# S7CAS-PLEIADES-CARTE-MERE_P20_DAC.net
KiCad netlist of a schematic drawn in Altium Designer
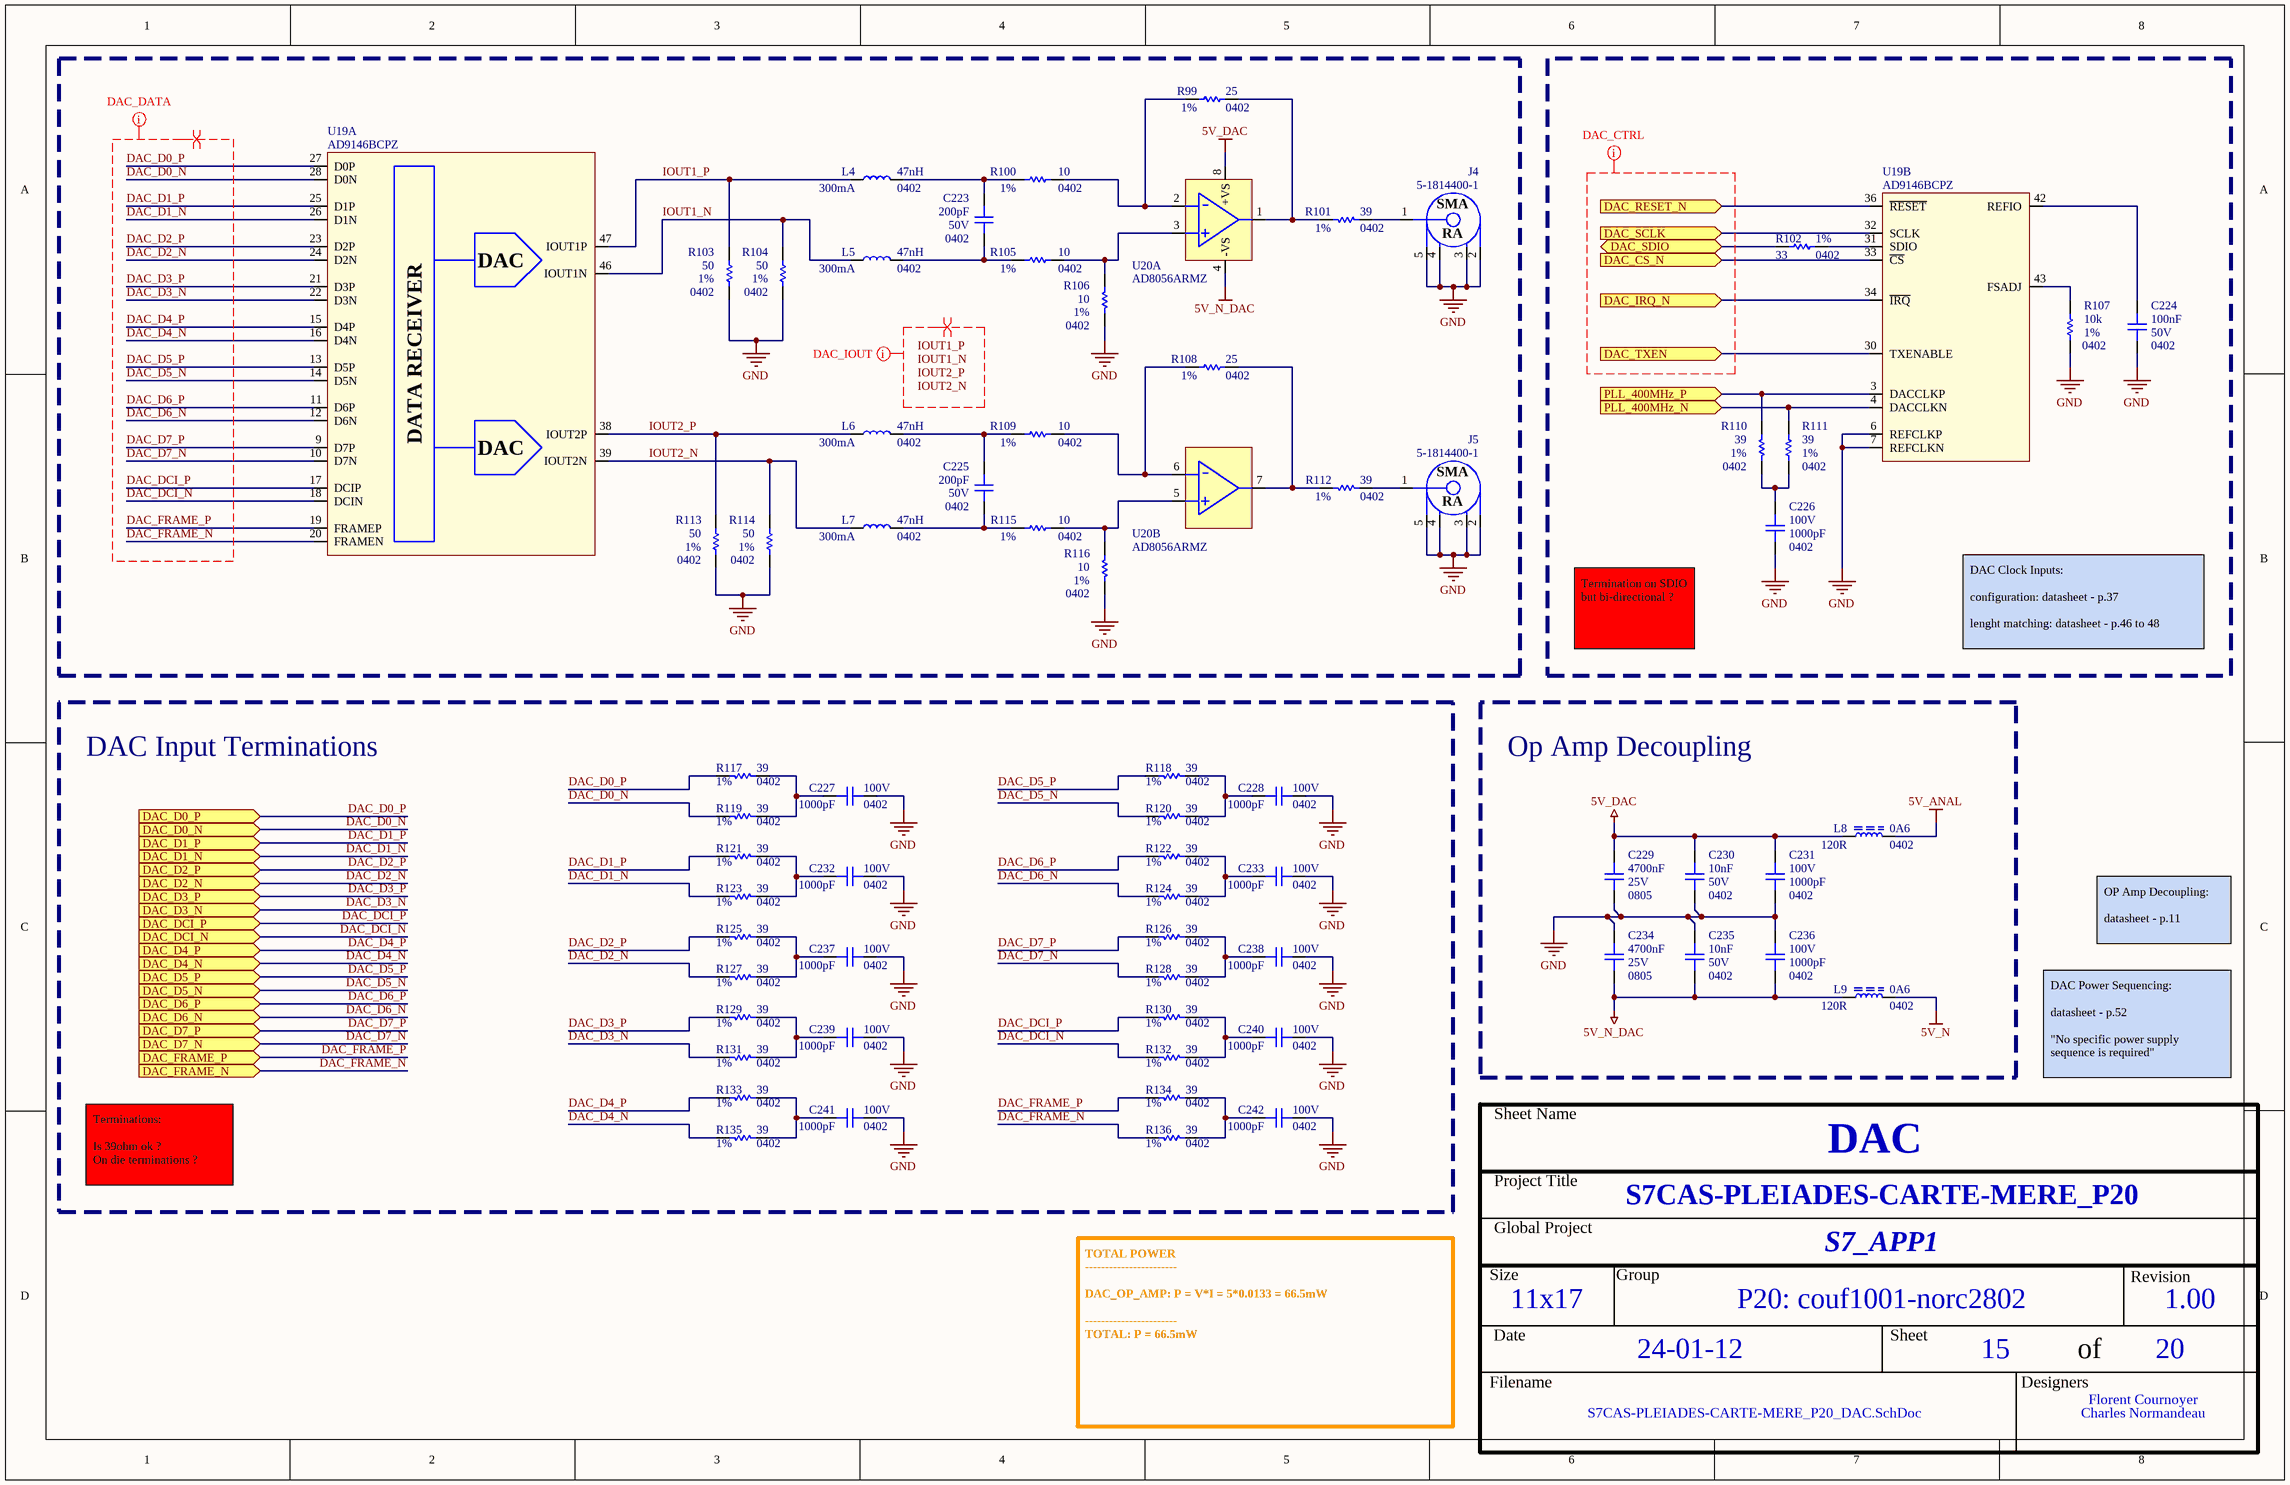
[diagram p0: S7CAS-PLEIADES-CARTE-MERE_P20_DAC.SchDoc]

(export (version "E")
  (design (tool "Eeschema 10.0.6"))
  (components
    (comp (ref "C223")
      (value "200pF")
      (footprint "CAP_0402")
      (description "CAP - 0402")
      (fields
        (field (name "MFG PART NUMBER") "GCM1555G1H201GA16")
        (field (name "VOLTAGE") "50V")
        (field (name "PACKAGE") "0402")
        (field (name "CREATEDBY") "Jonathan Bouchard")
      )
      (libsource (lib "S7CAS_LIB2023") (part "CAP - 0402"))
    )
    (comp (ref "C224")
      (value "100nF")
      (footprint "CAP_0402")
      (description "CAP - 0402")
      (fields
        (field (name "MFG PART NUMBER") "GRM155R61H104KE14")
        (field (name "VOLTAGE") "50V")
        (field (name "PACKAGE") "0402")
        (field (name "CREATEDBY") "Jonathan Bouchard")
      )
      (libsource (lib "S7CAS_LIB2023") (part "CAP - 0402"))
    )
    (comp (ref "C225")
      (value "200pF")
      (footprint "CAP_0402")
      (description "CAP - 0402")
      (fields
        (field (name "MFG PART NUMBER") "GCM1555G1H201GA16")
        (field (name "VOLTAGE") "50V")
        (field (name "PACKAGE") "0402")
        (field (name "CREATEDBY") "Jonathan Bouchard")
      )
      (libsource (lib "S7CAS_LIB2023") (part "CAP - 0402"))
    )
    (comp (ref "C226")
      (value "1000pF")
      (footprint "CAP_0402")
      (description "CAP - 0402")
      (fields
        (field (name "MFG PART NUMBER") "GRM155R72A102KA01")
        (field (name "VOLTAGE") "100V")
        (field (name "PACKAGE") "0402")
        (field (name "CREATEDBY") "Jonathan Bouchard")
      )
      (libsource (lib "S7CAS_LIB2023") (part "CAP - 0402"))
    )
    (comp (ref "C227")
      (value "1000pF")
      (footprint "CAP_0402")
      (description "CAP - 0402")
      (fields
        (field (name "MFG PART NUMBER") "GRM155R72A102KA01")
        (field (name "VOLTAGE") "100V")
        (field (name "PACKAGE") "0402")
        (field (name "CREATEDBY") "Jonathan Bouchard")
      )
      (libsource (lib "S7CAS_LIB2023") (part "CAP - 0402"))
    )
    (comp (ref "C228")
      (value "1000pF")
      (footprint "CAP_0402")
      (description "CAP - 0402")
      (fields
        (field (name "MFG PART NUMBER") "GRM155R72A102KA01")
        (field (name "VOLTAGE") "100V")
        (field (name "PACKAGE") "0402")
        (field (name "CREATEDBY") "Jonathan Bouchard")
      )
      (libsource (lib "S7CAS_LIB2023") (part "CAP - 0402"))
    )
    (comp (ref "C229")
      (value "4700nF")
      (footprint "CAP_0805")
      (description "CAP - 0805")
      (fields
        (field (name "MFG PART NUMBER") "GRM219R61E475KA73")
        (field (name "VOLTAGE") "25V")
        (field (name "PACKAGE") "0805")
        (field (name "CREATEDBY") "Jonathan Bouchard")
      )
      (libsource (lib "S7CAS_LIB2023") (part "CAP - 0805"))
    )
    (comp (ref "C230")
      (value "10nF")
      (footprint "CAP_0402")
      (description "CAP - 0402")
      (fields
        (field (name "MFG PART NUMBER") "GCM155R71H103KA55")
        (field (name "VOLTAGE") "50V")
        (field (name "PACKAGE") "0402")
        (field (name "CREATEDBY") "Jonathan Bouchard")
      )
      (libsource (lib "S7CAS_LIB2023") (part "CAP - 0402"))
    )
    (comp (ref "C231")
      (value "1000pF")
      (footprint "CAP_0402")
      (description "CAP - 0402")
      (fields
        (field (name "MFG PART NUMBER") "GRM155R72A102KA01")
        (field (name "VOLTAGE") "100V")
        (field (name "PACKAGE") "0402")
        (field (name "CREATEDBY") "Jonathan Bouchard")
      )
      (libsource (lib "S7CAS_LIB2023") (part "CAP - 0402"))
    )
    (comp (ref "C232")
      (value "1000pF")
      (footprint "CAP_0402")
      (description "CAP - 0402")
      (fields
        (field (name "MFG PART NUMBER") "GRM155R72A102KA01")
        (field (name "VOLTAGE") "100V")
        (field (name "PACKAGE") "0402")
        (field (name "CREATEDBY") "Jonathan Bouchard")
      )
      (libsource (lib "S7CAS_LIB2023") (part "CAP - 0402"))
    )
    (comp (ref "C233")
      (value "1000pF")
      (footprint "CAP_0402")
      (description "CAP - 0402")
      (fields
        (field (name "MFG PART NUMBER") "GRM155R72A102KA01")
        (field (name "VOLTAGE") "100V")
        (field (name "PACKAGE") "0402")
        (field (name "CREATEDBY") "Jonathan Bouchard")
      )
      (libsource (lib "S7CAS_LIB2023") (part "CAP - 0402"))
    )
    (comp (ref "C234")
      (value "4700nF")
      (footprint "CAP_0805")
      (description "CAP - 0805")
      (fields
        (field (name "MFG PART NUMBER") "GRM219R61E475KA73")
        (field (name "VOLTAGE") "25V")
        (field (name "PACKAGE") "0805")
        (field (name "CREATEDBY") "Jonathan Bouchard")
      )
      (libsource (lib "S7CAS_LIB2023") (part "CAP - 0805"))
    )
    (comp (ref "C235")
      (value "10nF")
      (footprint "CAP_0402")
      (description "CAP - 0402")
      (fields
        (field (name "MFG PART NUMBER") "GCM155R71H103KA55")
        (field (name "VOLTAGE") "50V")
        (field (name "PACKAGE") "0402")
        (field (name "CREATEDBY") "Jonathan Bouchard")
      )
      (libsource (lib "S7CAS_LIB2023") (part "CAP - 0402"))
    )
    (comp (ref "C236")
      (value "1000pF")
      (footprint "CAP_0402")
      (description "CAP - 0402")
      (fields
        (field (name "MFG PART NUMBER") "GRM155R72A102KA01")
        (field (name "VOLTAGE") "100V")
        (field (name "PACKAGE") "0402")
        (field (name "CREATEDBY") "Jonathan Bouchard")
      )
      (libsource (lib "S7CAS_LIB2023") (part "CAP - 0402"))
    )
    (comp (ref "C237")
      (value "1000pF")
      (footprint "CAP_0402")
      (description "CAP - 0402")
      (fields
        (field (name "MFG PART NUMBER") "GRM155R72A102KA01")
        (field (name "VOLTAGE") "100V")
        (field (name "PACKAGE") "0402")
        (field (name "CREATEDBY") "Jonathan Bouchard")
      )
      (libsource (lib "S7CAS_LIB2023") (part "CAP - 0402"))
    )
    (comp (ref "C238")
      (value "1000pF")
      (footprint "CAP_0402")
      (description "CAP - 0402")
      (fields
        (field (name "MFG PART NUMBER") "GRM155R72A102KA01")
        (field (name "VOLTAGE") "100V")
        (field (name "PACKAGE") "0402")
        (field (name "CREATEDBY") "Jonathan Bouchard")
      )
      (libsource (lib "S7CAS_LIB2023") (part "CAP - 0402"))
    )
    (comp (ref "C239")
      (value "1000pF")
      (footprint "CAP_0402")
      (description "CAP - 0402")
      (fields
        (field (name "MFG PART NUMBER") "GRM155R72A102KA01")
        (field (name "VOLTAGE") "100V")
        (field (name "PACKAGE") "0402")
        (field (name "CREATEDBY") "Jonathan Bouchard")
      )
      (libsource (lib "S7CAS_LIB2023") (part "CAP - 0402"))
    )
    (comp (ref "C240")
      (value "1000pF")
      (footprint "CAP_0402")
      (description "CAP - 0402")
      (fields
        (field (name "MFG PART NUMBER") "GRM155R72A102KA01")
        (field (name "VOLTAGE") "100V")
        (field (name "PACKAGE") "0402")
        (field (name "CREATEDBY") "Jonathan Bouchard")
      )
      (libsource (lib "S7CAS_LIB2023") (part "CAP - 0402"))
    )
    (comp (ref "C241")
      (value "1000pF")
      (footprint "CAP_0402")
      (description "CAP - 0402")
      (fields
        (field (name "MFG PART NUMBER") "GRM155R72A102KA01")
        (field (name "VOLTAGE") "100V")
        (field (name "PACKAGE") "0402")
        (field (name "CREATEDBY") "Jonathan Bouchard")
      )
      (libsource (lib "S7CAS_LIB2023") (part "CAP - 0402"))
    )
    (comp (ref "C242")
      (value "1000pF")
      (footprint "CAP_0402")
      (description "CAP - 0402")
      (fields
        (field (name "MFG PART NUMBER") "GRM155R72A102KA01")
        (field (name "VOLTAGE") "100V")
        (field (name "PACKAGE") "0402")
        (field (name "CREATEDBY") "Jonathan Bouchard")
      )
      (libsource (lib "S7CAS_LIB2023") (part "CAP - 0402"))
    )
    (comp (ref "J4")
      (value "5-1814400-1")
      (footprint "CONN_SMA_5-1814400-1")
      (description "CONN -  SMA JACK R/A 50 OHM - TH")
      (fields
        (field (name "MFG") "TE Connectivity AMP Connectors")
        (field (name "CREATEDBY") "Jonathan Bouchard")
      )
      (libsource (lib "S7CAS_LIB2023") (part "CONN_SMA_5-1814400-1"))
    )
    (comp (ref "J5")
      (value "5-1814400-1")
      (footprint "CONN_SMA_5-1814400-1")
      (description "CONN -  SMA JACK R/A 50 OHM - TH")
      (fields
        (field (name "MFG") "TE Connectivity AMP Connectors")
        (field (name "CREATEDBY") "Jonathan Bouchard")
      )
      (libsource (lib "S7CAS_LIB2023") (part "CONN_SMA_5-1814400-1"))
    )
    (comp (ref "L4")
      (value "47nH")
      (footprint "IND_0402")
      (description "IND - 0402")
      (fields
        (field (name "MFG PART NUMBER") "TBD")
        (field (name "CURRENT") "300mA")
        (field (name "PACKAGE") "0402")
        (field (name "Comment") "Part Number")
      )
      (libsource (lib "LIB_TEMP_P20_FLORENT_COURNOYER_SCH") (part "IND - 0402"))
    )
    (comp (ref "L5")
      (value "47nH")
      (footprint "IND_0402")
      (description "IND - 0402")
      (fields
        (field (name "MFG PART NUMBER") "TBD")
        (field (name "CURRENT") "300mA")
        (field (name "PACKAGE") "0402")
        (field (name "Comment") "Part Number")
      )
      (libsource (lib "LIB_TEMP_P20_FLORENT_COURNOYER_SCH") (part "IND - 0402"))
    )
    (comp (ref "L6")
      (value "47nH")
      (footprint "IND_0402")
      (description "IND - 0402")
      (fields
        (field (name "MFG PART NUMBER") "TBD")
        (field (name "CURRENT") "300mA")
        (field (name "PACKAGE") "0402")
        (field (name "Comment") "Part Number")
      )
      (libsource (lib "LIB_TEMP_P20_FLORENT_COURNOYER_SCH") (part "IND - 0402"))
    )
    (comp (ref "L7")
      (value "47nH")
      (footprint "IND_0402")
      (description "IND - 0402")
      (fields
        (field (name "MFG PART NUMBER") "TBD")
        (field (name "CURRENT") "300mA")
        (field (name "PACKAGE") "0402")
        (field (name "Comment") "Part Number")
      )
      (libsource (lib "LIB_TEMP_P20_FLORENT_COURNOYER_SCH") (part "IND - 0402"))
    )
    (comp (ref "L8")
      (value "120R")
      (footprint "FER_0402")
      (description "FER - 0402")
      (fields
        (field (name "MFG PART NUMBER") "BLM15BX121SN1")
        (field (name "CURRENT") "0A6")
        (field (name "PACKAGE") "0402")
        (field (name "CREATEDBY") "Jonathan Bouchard")
      )
      (libsource (lib "S7CAS_LIB2023") (part "FER - 0402"))
    )
    (comp (ref "L9")
      (value "120R")
      (footprint "FER_0402")
      (description "FER - 0402")
      (fields
        (field (name "MFG PART NUMBER") "BLM15BX121SN1")
        (field (name "CURRENT") "0A6")
        (field (name "PACKAGE") "0402")
        (field (name "CREATEDBY") "Jonathan Bouchard")
      )
      (libsource (lib "S7CAS_LIB2023") (part "FER - 0402"))
    )
    (comp (ref "R99")
      (value "25")
      (footprint "RES_0402")
      (description "RES - 0402")
      (fields
        (field (name "VOLTAGE") "50V")
        (field (name "MFG PART NUMBER") "CH0402-25RJFT")
        (field (name "PACKAGE") "0402")
        (field (name "PRECISION") "1%")
        (field (name "CREATEDBY") "Jonathan Bouchard")
      )
      (libsource (lib "S7CAS_LIB2023") (part "RES - 0402"))
    )
    (comp (ref "R100")
      (value "10")
      (footprint "RES_0402")
      (description "RES - 0402")
      (fields
        (field (name "VOLTAGE") "50V")
        (field (name "MFG PART NUMBER") "RN73H1ETTP10R1F50")
        (field (name "PACKAGE") "0402")
        (field (name "PRECISION") "1%")
        (field (name "CREATEDBY") "Jonathan Bouchard")
      )
      (libsource (lib "S7CAS_LIB2023") (part "RES - 0402"))
    )
    (comp (ref "R101")
      (value "39")
      (footprint "RES_0402")
      (description "RES - 0402")
      (fields
        (field (name "VOLTAGE") "50")
        (field (name "MFG PART NUMBER") "RL0510S-390-F")
        (field (name "PACKAGE") "0402")
        (field (name "PRECISION") "1%")
        (field (name "CREATEDBY") "Jonathan Bouchard")
      )
      (libsource (lib "S7CAS_LIB2023") (part "RES - 0402"))
    )
    (comp (ref "R102")
      (value "33")
      (footprint "RES_0402")
      (description "RES - 0402")
      (fields
        (field (name "VOLTAGE") "50V")
        (field (name "MFG PART NUMBER") "CRCW040233R0FKEDC")
        (field (name "PACKAGE") "0402")
        (field (name "PRECISION") "1%")
        (field (name "CREATEDBY") "Jonathan Bouchard")
      )
      (libsource (lib "S7CAS_LIB2023") (part "RES - 0402"))
    )
    (comp (ref "R103")
      (value "50")
      (footprint "RES_0402")
      (description "RES - 0402")
      (fields
        (field (name "MFG PART NUMBER") "MIC5000BFLMGNHWS")
        (field (name "POWER") "1/8W")
        (field (name "PACKAGE") "0402")
        (field (name "PRECISION") "1%")
        (field (name "CREATEDBY") "Jonathan Bouchard")
      )
      (libsource (lib "S7CAS_LIB2023") (part "RES - 0402"))
    )
    (comp (ref "R104")
      (value "50")
      (footprint "RES_0402")
      (description "RES - 0402")
      (fields
        (field (name "MFG PART NUMBER") "MIC5000BFLMGNHWS")
        (field (name "POWER") "1/8W")
        (field (name "PACKAGE") "0402")
        (field (name "PRECISION") "1%")
        (field (name "CREATEDBY") "Jonathan Bouchard")
      )
      (libsource (lib "S7CAS_LIB2023") (part "RES - 0402"))
    )
    (comp (ref "R105")
      (value "10")
      (footprint "RES_0402")
      (description "RES - 0402")
      (fields
        (field (name "VOLTAGE") "50V")
        (field (name "MFG PART NUMBER") "RN73H1ETTP10R1F50")
        (field (name "PACKAGE") "0402")
        (field (name "PRECISION") "1%")
        (field (name "CREATEDBY") "Jonathan Bouchard")
      )
      (libsource (lib "S7CAS_LIB2023") (part "RES - 0402"))
    )
    (comp (ref "R106")
      (value "10")
      (footprint "RES_0402")
      (description "RES - 0402")
      (fields
        (field (name "VOLTAGE") "50V")
        (field (name "MFG PART NUMBER") "RN73H1ETTP10R1F50")
        (field (name "PACKAGE") "0402")
        (field (name "PRECISION") "1%")
        (field (name "CREATEDBY") "Jonathan Bouchard")
      )
      (libsource (lib "S7CAS_LIB2023") (part "RES - 0402"))
    )
    (comp (ref "R107")
      (value "10k")
      (footprint "RES_0402")
      (description "RES - 0402")
      (fields
        (field (name "VOLTAGE") "50V")
        (field (name "MFG PART NUMBER") "MCS04020C1002FE000")
        (field (name "PACKAGE") "0402")
        (field (name "PRECISION") "1%")
        (field (name "CREATEDBY") "Jonathan Bouchard")
      )
      (libsource (lib "S7CAS_LIB2023") (part "RES - 0402"))
    )
    (comp (ref "R108")
      (value "25")
      (footprint "RES_0402")
      (description "RES - 0402")
      (fields
        (field (name "VOLTAGE") "50V")
        (field (name "MFG PART NUMBER") "CH0402-25RJFT")
        (field (name "PACKAGE") "0402")
        (field (name "PRECISION") "1%")
        (field (name "CREATEDBY") "Jonathan Bouchard")
      )
      (libsource (lib "S7CAS_LIB2023") (part "RES - 0402"))
    )
    (comp (ref "R109")
      (value "10")
      (footprint "RES_0402")
      (description "RES - 0402")
      (fields
        (field (name "VOLTAGE") "50V")
        (field (name "MFG PART NUMBER") "RN73H1ETTP10R1F50")
        (field (name "PACKAGE") "0402")
        (field (name "PRECISION") "1%")
        (field (name "CREATEDBY") "Jonathan Bouchard")
      )
      (libsource (lib "S7CAS_LIB2023") (part "RES - 0402"))
    )
    (comp (ref "R110")
      (value "39")
      (footprint "RES_0402")
      (description "RES - 0402")
      (fields
        (field (name "VOLTAGE") "50")
        (field (name "MFG PART NUMBER") "RL0510S-390-F")
        (field (name "PACKAGE") "0402")
        (field (name "PRECISION") "1%")
        (field (name "CREATEDBY") "Jonathan Bouchard")
      )
      (libsource (lib "S7CAS_LIB2023") (part "RES - 0402"))
    )
    (comp (ref "R111")
      (value "39")
      (footprint "RES_0402")
      (description "RES - 0402")
      (fields
        (field (name "VOLTAGE") "50")
        (field (name "MFG PART NUMBER") "RL0510S-390-F")
        (field (name "PACKAGE") "0402")
        (field (name "PRECISION") "1%")
        (field (name "CREATEDBY") "Jonathan Bouchard")
      )
      (libsource (lib "S7CAS_LIB2023") (part "RES - 0402"))
    )
    (comp (ref "R112")
      (value "39")
      (footprint "RES_0402")
      (description "RES - 0402")
      (fields
        (field (name "VOLTAGE") "50")
        (field (name "MFG PART NUMBER") "RL0510S-390-F")
        (field (name "PACKAGE") "0402")
        (field (name "PRECISION") "1%")
        (field (name "CREATEDBY") "Jonathan Bouchard")
      )
      (libsource (lib "S7CAS_LIB2023") (part "RES - 0402"))
    )
    (comp (ref "R113")
      (value "50")
      (footprint "RES_0402")
      (description "RES - 0402")
      (fields
        (field (name "MFG PART NUMBER") "MIC5000BFLMGNHWS")
        (field (name "POWER") "1/8W")
        (field (name "PACKAGE") "0402")
        (field (name "PRECISION") "1%")
        (field (name "CREATEDBY") "Jonathan Bouchard")
      )
      (libsource (lib "S7CAS_LIB2023") (part "RES - 0402"))
    )
    (comp (ref "R114")
      (value "50")
      (footprint "RES_0402")
      (description "RES - 0402")
      (fields
        (field (name "MFG PART NUMBER") "MIC5000BFLMGNHWS")
        (field (name "POWER") "1/8W")
        (field (name "PACKAGE") "0402")
        (field (name "PRECISION") "1%")
        (field (name "CREATEDBY") "Jonathan Bouchard")
      )
      (libsource (lib "S7CAS_LIB2023") (part "RES - 0402"))
    )
    (comp (ref "R115")
      (value "10")
      (footprint "RES_0402")
      (description "RES - 0402")
      (fields
        (field (name "VOLTAGE") "50V")
        (field (name "MFG PART NUMBER") "RN73H1ETTP10R1F50")
        (field (name "PACKAGE") "0402")
        (field (name "PRECISION") "1%")
        (field (name "CREATEDBY") "Jonathan Bouchard")
      )
      (libsource (lib "S7CAS_LIB2023") (part "RES - 0402"))
    )
    (comp (ref "R116")
      (value "10")
      (footprint "RES_0402")
      (description "RES - 0402")
      (fields
        (field (name "VOLTAGE") "50V")
        (field (name "MFG PART NUMBER") "RN73H1ETTP10R1F50")
        (field (name "PACKAGE") "0402")
        (field (name "PRECISION") "1%")
        (field (name "CREATEDBY") "Jonathan Bouchard")
      )
      (libsource (lib "S7CAS_LIB2023") (part "RES - 0402"))
    )
    (comp (ref "R117")
      (value "39")
      (footprint "RES_0402")
      (description "RES - 0402")
      (fields
        (field (name "VOLTAGE") "50")
        (field (name "MFG PART NUMBER") "RL0510S-390-F")
        (field (name "PACKAGE") "0402")
        (field (name "PRECISION") "1%")
        (field (name "CREATEDBY") "Jonathan Bouchard")
      )
      (libsource (lib "S7CAS_LIB2023") (part "RES - 0402"))
    )
    (comp (ref "R118")
      (value "39")
      (footprint "RES_0402")
      (description "RES - 0402")
      (fields
        (field (name "VOLTAGE") "50")
        (field (name "MFG PART NUMBER") "RL0510S-390-F")
        (field (name "PACKAGE") "0402")
        (field (name "PRECISION") "1%")
        (field (name "CREATEDBY") "Jonathan Bouchard")
      )
      (libsource (lib "S7CAS_LIB2023") (part "RES - 0402"))
    )
    (comp (ref "R119")
      (value "39")
      (footprint "RES_0402")
      (description "RES - 0402")
      (fields
        (field (name "VOLTAGE") "50")
        (field (name "MFG PART NUMBER") "RL0510S-390-F")
        (field (name "PACKAGE") "0402")
        (field (name "PRECISION") "1%")
        (field (name "CREATEDBY") "Jonathan Bouchard")
      )
      (libsource (lib "S7CAS_LIB2023") (part "RES - 0402"))
    )
    (comp (ref "R120")
      (value "39")
      (footprint "RES_0402")
      (description "RES - 0402")
      (fields
        (field (name "VOLTAGE") "50")
        (field (name "MFG PART NUMBER") "RL0510S-390-F")
        (field (name "PACKAGE") "0402")
        (field (name "PRECISION") "1%")
        (field (name "CREATEDBY") "Jonathan Bouchard")
      )
      (libsource (lib "S7CAS_LIB2023") (part "RES - 0402"))
    )
    (comp (ref "R121")
      (value "39")
      (footprint "RES_0402")
      (description "RES - 0402")
      (fields
        (field (name "VOLTAGE") "50")
        (field (name "MFG PART NUMBER") "RL0510S-390-F")
        (field (name "PACKAGE") "0402")
        (field (name "PRECISION") "1%")
        (field (name "CREATEDBY") "Jonathan Bouchard")
      )
      (libsource (lib "S7CAS_LIB2023") (part "RES - 0402"))
    )
    (comp (ref "R122")
      (value "39")
      (footprint "RES_0402")
      (description "RES - 0402")
      (fields
        (field (name "VOLTAGE") "50")
        (field (name "MFG PART NUMBER") "RL0510S-390-F")
        (field (name "PACKAGE") "0402")
        (field (name "PRECISION") "1%")
        (field (name "CREATEDBY") "Jonathan Bouchard")
      )
      (libsource (lib "S7CAS_LIB2023") (part "RES - 0402"))
    )
    (comp (ref "R123")
      (value "39")
      (footprint "RES_0402")
      (description "RES - 0402")
      (fields
        (field (name "VOLTAGE") "50")
        (field (name "MFG PART NUMBER") "RL0510S-390-F")
        (field (name "PACKAGE") "0402")
        (field (name "PRECISION") "1%")
        (field (name "CREATEDBY") "Jonathan Bouchard")
      )
      (libsource (lib "S7CAS_LIB2023") (part "RES - 0402"))
    )
    (comp (ref "R124")
      (value "39")
      (footprint "RES_0402")
      (description "RES - 0402")
      (fields
        (field (name "VOLTAGE") "50")
        (field (name "MFG PART NUMBER") "RL0510S-390-F")
        (field (name "PACKAGE") "0402")
        (field (name "PRECISION") "1%")
        (field (name "CREATEDBY") "Jonathan Bouchard")
      )
      (libsource (lib "S7CAS_LIB2023") (part "RES - 0402"))
    )
    (comp (ref "R125")
      (value "39")
      (footprint "RES_0402")
      (description "RES - 0402")
      (fields
        (field (name "VOLTAGE") "50")
        (field (name "MFG PART NUMBER") "RL0510S-390-F")
        (field (name "PACKAGE") "0402")
        (field (name "PRECISION") "1%")
        (field (name "CREATEDBY") "Jonathan Bouchard")
      )
      (libsource (lib "S7CAS_LIB2023") (part "RES - 0402"))
    )
    (comp (ref "R126")
      (value "39")
      (footprint "RES_0402")
      (description "RES - 0402")
      (fields
        (field (name "VOLTAGE") "50")
        (field (name "MFG PART NUMBER") "RL0510S-390-F")
        (field (name "PACKAGE") "0402")
        (field (name "PRECISION") "1%")
        (field (name "CREATEDBY") "Jonathan Bouchard")
      )
      (libsource (lib "S7CAS_LIB2023") (part "RES - 0402"))
    )
    (comp (ref "R127")
      (value "39")
      (footprint "RES_0402")
      (description "RES - 0402")
      (fields
        (field (name "VOLTAGE") "50")
        (field (name "MFG PART NUMBER") "RL0510S-390-F")
        (field (name "PACKAGE") "0402")
        (field (name "PRECISION") "1%")
        (field (name "CREATEDBY") "Jonathan Bouchard")
      )
      (libsource (lib "S7CAS_LIB2023") (part "RES - 0402"))
    )
    (comp (ref "R128")
      (value "39")
      (footprint "RES_0402")
      (description "RES - 0402")
      (fields
        (field (name "VOLTAGE") "50")
        (field (name "MFG PART NUMBER") "RL0510S-390-F")
        (field (name "PACKAGE") "0402")
        (field (name "PRECISION") "1%")
        (field (name "CREATEDBY") "Jonathan Bouchard")
      )
      (libsource (lib "S7CAS_LIB2023") (part "RES - 0402"))
    )
    (comp (ref "R129")
      (value "39")
      (footprint "RES_0402")
      (description "RES - 0402")
      (fields
        (field (name "VOLTAGE") "50")
        (field (name "MFG PART NUMBER") "RL0510S-390-F")
        (field (name "PACKAGE") "0402")
        (field (name "PRECISION") "1%")
        (field (name "CREATEDBY") "Jonathan Bouchard")
      )
      (libsource (lib "S7CAS_LIB2023") (part "RES - 0402"))
    )
    (comp (ref "R130")
      (value "39")
      (footprint "RES_0402")
      (description "RES - 0402")
      (fields
        (field (name "VOLTAGE") "50")
        (field (name "MFG PART NUMBER") "RL0510S-390-F")
        (field (name "PACKAGE") "0402")
        (field (name "PRECISION") "1%")
        (field (name "CREATEDBY") "Jonathan Bouchard")
      )
      (libsource (lib "S7CAS_LIB2023") (part "RES - 0402"))
    )
    (comp (ref "R131")
      (value "39")
      (footprint "RES_0402")
      (description "RES - 0402")
      (fields
        (field (name "VOLTAGE") "50")
        (field (name "MFG PART NUMBER") "RL0510S-390-F")
        (field (name "PACKAGE") "0402")
        (field (name "PRECISION") "1%")
        (field (name "CREATEDBY") "Jonathan Bouchard")
      )
      (libsource (lib "S7CAS_LIB2023") (part "RES - 0402"))
    )
    (comp (ref "R132")
      (value "39")
      (footprint "RES_0402")
      (description "RES - 0402")
      (fields
        (field (name "VOLTAGE") "50")
        (field (name "MFG PART NUMBER") "RL0510S-390-F")
        (field (name "PACKAGE") "0402")
        (field (name "PRECISION") "1%")
        (field (name "CREATEDBY") "Jonathan Bouchard")
      )
      (libsource (lib "S7CAS_LIB2023") (part "RES - 0402"))
    )
    (comp (ref "R133")
      (value "39")
      (footprint "RES_0402")
      (description "RES - 0402")
      (fields
        (field (name "VOLTAGE") "50")
        (field (name "MFG PART NUMBER") "RL0510S-390-F")
        (field (name "PACKAGE") "0402")
        (field (name "PRECISION") "1%")
        (field (name "CREATEDBY") "Jonathan Bouchard")
      )
      (libsource (lib "S7CAS_LIB2023") (part "RES - 0402"))
    )
    (comp (ref "R134")
      (value "39")
      (footprint "RES_0402")
      (description "RES - 0402")
      (fields
        (field (name "VOLTAGE") "50")
        (field (name "MFG PART NUMBER") "RL0510S-390-F")
        (field (name "PACKAGE") "0402")
        (field (name "PRECISION") "1%")
        (field (name "CREATEDBY") "Jonathan Bouchard")
      )
      (libsource (lib "S7CAS_LIB2023") (part "RES - 0402"))
    )
    (comp (ref "R135")
      (value "39")
      (footprint "RES_0402")
      (description "RES - 0402")
      (fields
        (field (name "VOLTAGE") "50")
        (field (name "MFG PART NUMBER") "RL0510S-390-F")
        (field (name "PACKAGE") "0402")
        (field (name "PRECISION") "1%")
        (field (name "CREATEDBY") "Jonathan Bouchard")
      )
      (libsource (lib "S7CAS_LIB2023") (part "RES - 0402"))
    )
    (comp (ref "R136")
      (value "39")
      (footprint "RES_0402")
      (description "RES - 0402")
      (fields
        (field (name "VOLTAGE") "50")
        (field (name "MFG PART NUMBER") "RL0510S-390-F")
        (field (name "PACKAGE") "0402")
        (field (name "PRECISION") "1%")
        (field (name "CREATEDBY") "Jonathan Bouchard")
      )
      (libsource (lib "S7CAS_LIB2023") (part "RES - 0402"))
    )
    (comp (ref "U19")
      (value "AD9146BCPZ")
      (footprint "DAC_AD9146BCPZ")
      (description "DAC - 16BIT SRL HIGH SPEED - QFN-48")
      (fields
        (field (name "VOLTAGE") "3.13 V ~ 3.47 V / 1.71 V ~ 1.89 V")
        (field (name "MFG") "Analog Devices Inc.")
        (field (name "CREATEDBY") "Jonathan Bouchard")
      )
      (libsource (lib "S7CAS_LIB2023") (part "DAC_AD9146BCPZ"))
    )
    (comp (ref "U20")
      (value "AD8056ARMZ")
      (footprint "OPAMP_AD8056ARMZ")
      (description "OPAMP - VFB 300MHZ - 8MSOP")
      (fields
        (field (name "VOLTAGE") "8 V ~ 12 V, ±4 V ~ 6 V")
        (field (name "MFG") "Analog Devices")
        (field (name "CREATEDBY") "Jonathan Bouchard")
      )
      (libsource (lib "S7CAS_LIB2023") (part "OPAMP_AD8056ARMZ"))
    )
  )
  (nets
    (net (code "1") (name "/DAC_CS_N") (class "Default")
      (node (ref "U19") (pin "33") (pinfunction "~{CS}_33") (pintype "passive"))
    )
    (net (code "2") (name "/DAC_D0_N") (class "Default")
      (node (ref "R119") (pin "1") (pinfunction "1_1") (pintype "passive"))
      (node (ref "U19") (pin "28") (pinfunction "D0N_28") (pintype "passive"))
    )
    (net (code "3") (name "/DAC_D0_P") (class "Default")
      (node (ref "R117") (pin "1") (pinfunction "1_1") (pintype "passive"))
      (node (ref "U19") (pin "27") (pinfunction "D0P_27") (pintype "passive"))
    )
    (net (code "4") (name "/DAC_D1_N") (class "Default")
      (node (ref "R123") (pin "1") (pinfunction "1_1") (pintype "passive"))
      (node (ref "U19") (pin "26") (pinfunction "D1N_26") (pintype "passive"))
    )
    (net (code "5") (name "/DAC_D1_P") (class "Default")
      (node (ref "R121") (pin "1") (pinfunction "1_1") (pintype "passive"))
      (node (ref "U19") (pin "25") (pinfunction "D1P_25") (pintype "passive"))
    )
    (net (code "6") (name "/DAC_D2_N") (class "Default")
      (node (ref "R127") (pin "1") (pinfunction "1_1") (pintype "passive"))
      (node (ref "U19") (pin "24") (pinfunction "D2N_24") (pintype "passive"))
    )
    (net (code "7") (name "/DAC_D2_P") (class "Default")
      (node (ref "R125") (pin "1") (pinfunction "1_1") (pintype "passive"))
      (node (ref "U19") (pin "23") (pinfunction "D2P_23") (pintype "passive"))
    )
    (net (code "8") (name "/DAC_D3_N") (class "Default")
      (node (ref "R131") (pin "1") (pinfunction "1_1") (pintype "passive"))
      (node (ref "U19") (pin "22") (pinfunction "D3N_22") (pintype "passive"))
    )
    (net (code "9") (name "/DAC_D3_P") (class "Default")
      (node (ref "R129") (pin "1") (pinfunction "1_1") (pintype "passive"))
      (node (ref "U19") (pin "21") (pinfunction "D3P_21") (pintype "passive"))
    )
    (net (code "10") (name "/DAC_D4_N") (class "Default")
      (node (ref "R135") (pin "1") (pinfunction "1_1") (pintype "passive"))
      (node (ref "U19") (pin "16") (pinfunction "D4N_16") (pintype "passive"))
    )
    (net (code "11") (name "/DAC_D4_P") (class "Default")
      (node (ref "R133") (pin "1") (pinfunction "1_1") (pintype "passive"))
      (node (ref "U19") (pin "15") (pinfunction "D4P_15") (pintype "passive"))
    )
    (net (code "12") (name "/DAC_D5_N") (class "Default")
      (node (ref "R120") (pin "1") (pinfunction "1_1") (pintype "passive"))
      (node (ref "U19") (pin "14") (pinfunction "D5N_14") (pintype "passive"))
    )
    (net (code "13") (name "/DAC_D5_P") (class "Default")
      (node (ref "R118") (pin "1") (pinfunction "1_1") (pintype "passive"))
      (node (ref "U19") (pin "13") (pinfunction "D5P_13") (pintype "passive"))
    )
    (net (code "14") (name "/DAC_D6_N") (class "Default")
      (node (ref "R124") (pin "1") (pinfunction "1_1") (pintype "passive"))
      (node (ref "U19") (pin "12") (pinfunction "D6N_12") (pintype "passive"))
    )
    (net (code "15") (name "/DAC_D6_P") (class "Default")
      (node (ref "R122") (pin "1") (pinfunction "1_1") (pintype "passive"))
      (node (ref "U19") (pin "11") (pinfunction "D6P_11") (pintype "passive"))
    )
    (net (code "16") (name "/DAC_D7_N") (class "Default")
      (node (ref "R128") (pin "1") (pinfunction "1_1") (pintype "passive"))
      (node (ref "U19") (pin "10") (pinfunction "D7N_10") (pintype "passive"))
    )
    (net (code "17") (name "/DAC_D7_P") (class "Default")
      (node (ref "R126") (pin "1") (pinfunction "1_1") (pintype "passive"))
      (node (ref "U19") (pin "9") (pinfunction "D7P_9") (pintype "passive"))
    )
    (net (code "18") (name "/DAC_DCI_N") (class "Default")
      (node (ref "R132") (pin "1") (pinfunction "1_1") (pintype "passive"))
      (node (ref "U19") (pin "18") (pinfunction "DCIN_18") (pintype "passive"))
    )
    (net (code "19") (name "/DAC_DCI_P") (class "Default")
      (node (ref "R130") (pin "1") (pinfunction "1_1") (pintype "passive"))
      (node (ref "U19") (pin "17") (pinfunction "DCIP_17") (pintype "passive"))
    )
    (net (code "20") (name "/DAC_FRAME_N") (class "Default")
      (node (ref "R136") (pin "1") (pinfunction "1_1") (pintype "passive"))
      (node (ref "U19") (pin "20") (pinfunction "FRAMEN_20") (pintype "passive"))
    )
    (net (code "21") (name "/DAC_FRAME_P") (class "Default")
      (node (ref "R134") (pin "1") (pinfunction "1_1") (pintype "passive"))
      (node (ref "U19") (pin "19") (pinfunction "FRAMEP_19") (pintype "passive"))
    )
    (net (code "22") (name "/DAC_IRQ_N") (class "Default")
      (node (ref "U19") (pin "34") (pinfunction "~{IRQ}_34") (pintype "passive"))
    )
    (net (code "23") (name "/DAC_RESET_N") (class "Default")
      (node (ref "U19") (pin "36") (pinfunction "~{RESET}_36") (pintype "passive"))
    )
    (net (code "24") (name "/DAC_SCLK") (class "Default")
      (node (ref "U19") (pin "32") (pinfunction "SCLK_32") (pintype "passive"))
    )
    (net (code "25") (name "/DAC_SDIO") (class "Default")
      (node (ref "R102") (pin "2") (pinfunction "2_2") (pintype "passive"))
    )
    (net (code "26") (name "/DAC_TXEN") (class "Default")
      (node (ref "U19") (pin "30") (pinfunction "TXENABLE_30") (pintype "passive"))
    )
    (net (code "27") (name "/IOUT1_N") (class "Default")
      (node (ref "L5") (pin "1") (pinfunction "1_1") (pintype "passive"))
      (node (ref "R104") (pin "1") (pinfunction "1_1") (pintype "passive"))
      (node (ref "U19") (pin "46") (pinfunction "IOUT1N_46") (pintype "passive"))
    )
    (net (code "28") (name "/IOUT1_P") (class "Default")
      (node (ref "L4") (pin "1") (pinfunction "1_1") (pintype "passive"))
      (node (ref "R103") (pin "1") (pinfunction "1_1") (pintype "passive"))
      (node (ref "U19") (pin "47") (pinfunction "IOUT1P_47") (pintype "passive"))
    )
    (net (code "29") (name "/IOUT2_N") (class "Default")
      (node (ref "L7") (pin "1") (pinfunction "1_1") (pintype "passive"))
      (node (ref "R114") (pin "1") (pinfunction "1_1") (pintype "passive"))
      (node (ref "U19") (pin "39") (pinfunction "IOUT2N_39") (pintype "passive"))
    )
    (net (code "30") (name "/IOUT2_P") (class "Default")
      (node (ref "L6") (pin "1") (pinfunction "1_1") (pintype "passive"))
      (node (ref "R113") (pin "1") (pinfunction "1_1") (pintype "passive"))
      (node (ref "U19") (pin "38") (pinfunction "IOUT2P_38") (pintype "passive"))
    )
    (net (code "31") (name "/PLL_400MHz_N") (class "Default")
      (node (ref "R111") (pin "2") (pinfunction "2_2") (pintype "passive"))
      (node (ref "U19") (pin "4") (pinfunction "DACCLKN_4") (pintype "passive"))
    )
    (net (code "32") (name "/PLL_400MHz_P") (class "Default")
      (node (ref "R110") (pin "2") (pinfunction "2_2") (pintype "passive"))
      (node (ref "U19") (pin "3") (pinfunction "DACCLKP_3") (pintype "passive"))
    )
    (net (code "33") (name "5V_ANAL") (class "Default")
      (node (ref "L8") (pin "1") (pinfunction "1_1") (pintype "passive"))
    )
    (net (code "34") (name "5V_DAC") (class "Default")
      (node (ref "C229") (pin "2") (pinfunction "2_2") (pintype "passive"))
      (node (ref "C230") (pin "2") (pinfunction "2_2") (pintype "passive"))
      (node (ref "C231") (pin "1") (pinfunction "1_1") (pintype "passive"))
      (node (ref "L8") (pin "2") (pinfunction "2_2") (pintype "passive"))
      (node (ref "U20") (pin "8") (pinfunction "+VS_8") (pintype "passive"))
    )
    (net (code "35") (name "5V_N") (class "Default")
      (node (ref "L9") (pin "1") (pinfunction "1_1") (pintype "passive"))
    )
    (net (code "36") (name "5V_N_DAC") (class "Default")
      (node (ref "C234") (pin "1") (pinfunction "1_1") (pintype "passive"))
      (node (ref "C235") (pin "1") (pinfunction "1_1") (pintype "passive"))
      (node (ref "C236") (pin "2") (pinfunction "2_2") (pintype "passive"))
      (node (ref "L9") (pin "2") (pinfunction "2_2") (pintype "passive"))
      (node (ref "U20") (pin "4") (pinfunction "-VS_4") (pintype "passive"))
    )
    (net (code "37") (name "GND") (class "Default")
      (node (ref "C224") (pin "1") (pinfunction "1_1") (pintype "passive"))
      (node (ref "C226") (pin "2") (pinfunction "2_2") (pintype "passive"))
      (node (ref "C227") (pin "1") (pinfunction "1_1") (pintype "passive"))
      (node (ref "C228") (pin "1") (pinfunction "1_1") (pintype "passive"))
      (node (ref "C229") (pin "1") (pinfunction "1_1") (pintype "passive"))
      (node (ref "C230") (pin "1") (pinfunction "1_1") (pintype "passive"))
      (node (ref "C231") (pin "2") (pinfunction "2_2") (pintype "passive"))
      (node (ref "C232") (pin "1") (pinfunction "1_1") (pintype "passive"))
      (node (ref "C233") (pin "1") (pinfunction "1_1") (pintype "passive"))
      (node (ref "C234") (pin "2") (pinfunction "2_2") (pintype "passive"))
      (node (ref "C235") (pin "2") (pinfunction "2_2") (pintype "passive"))
      (node (ref "C236") (pin "1") (pinfunction "1_1") (pintype "passive"))
      (node (ref "C237") (pin "1") (pinfunction "1_1") (pintype "passive"))
      (node (ref "C238") (pin "1") (pinfunction "1_1") (pintype "passive"))
      (node (ref "C239") (pin "1") (pinfunction "1_1") (pintype "passive"))
      (node (ref "C240") (pin "1") (pinfunction "1_1") (pintype "passive"))
      (node (ref "C241") (pin "1") (pinfunction "1_1") (pintype "passive"))
      (node (ref "C242") (pin "1") (pinfunction "1_1") (pintype "passive"))
      (node (ref "J4") (pin "2") (pinfunction "2_2") (pintype "passive"))
      (node (ref "J4") (pin "3") (pinfunction "3_3") (pintype "passive"))
      (node (ref "J4") (pin "4") (pinfunction "4_4") (pintype "passive"))
      (node (ref "J4") (pin "5") (pinfunction "5_5") (pintype "passive"))
      (node (ref "J5") (pin "2") (pinfunction "2_2") (pintype "passive"))
      (node (ref "J5") (pin "3") (pinfunction "3_3") (pintype "passive"))
      (node (ref "J5") (pin "4") (pinfunction "4_4") (pintype "passive"))
      (node (ref "J5") (pin "5") (pinfunction "5_5") (pintype "passive"))
      (node (ref "R103") (pin "2") (pinfunction "2_2") (pintype "passive"))
      (node (ref "R104") (pin "2") (pinfunction "2_2") (pintype "passive"))
      (node (ref "R106") (pin "1") (pinfunction "1_1") (pintype "passive"))
      (node (ref "R107") (pin "1") (pinfunction "1_1") (pintype "passive"))
      (node (ref "R113") (pin "2") (pinfunction "2_2") (pintype "passive"))
      (node (ref "R114") (pin "2") (pinfunction "2_2") (pintype "passive"))
      (node (ref "R116") (pin "1") (pinfunction "1_1") (pintype "passive"))
      (node (ref "U19") (pin "6") (pinfunction "REFCLKP_6") (pintype "passive"))
      (node (ref "U19") (pin "7") (pinfunction "REFCLKN_7") (pintype "passive"))
    )
    (net (code "38") (name "Net-(C223-Pad1)") (class "Default")
      (node (ref "C223") (pin "1") (pinfunction "1_1") (pintype "passive"))
      (node (ref "L5") (pin "2") (pinfunction "2_2") (pintype "passive"))
      (node (ref "R105") (pin "2") (pinfunction "2_2") (pintype "passive"))
    )
    (net (code "39") (name "Net-(C223-Pad2)") (class "Default")
      (node (ref "C223") (pin "2") (pinfunction "2_2") (pintype "passive"))
      (node (ref "L4") (pin "2") (pinfunction "2_2") (pintype "passive"))
      (node (ref "R100") (pin "2") (pinfunction "2_2") (pintype "passive"))
    )
    (net (code "40") (name "Net-(C225-Pad1)") (class "Default")
      (node (ref "C225") (pin "1") (pinfunction "1_1") (pintype "passive"))
      (node (ref "L7") (pin "2") (pinfunction "2_2") (pintype "passive"))
      (node (ref "R115") (pin "2") (pinfunction "2_2") (pintype "passive"))
    )
    (net (code "41") (name "Net-(C225-Pad2)") (class "Default")
      (node (ref "C225") (pin "2") (pinfunction "2_2") (pintype "passive"))
      (node (ref "L6") (pin "2") (pinfunction "2_2") (pintype "passive"))
      (node (ref "R109") (pin "2") (pinfunction "2_2") (pintype "passive"))
    )
    (net (code "42") (name "Net-(C226-Pad1)") (class "Default")
      (node (ref "C226") (pin "1") (pinfunction "1_1") (pintype "passive"))
      (node (ref "R110") (pin "1") (pinfunction "1_1") (pintype "passive"))
      (node (ref "R111") (pin "1") (pinfunction "1_1") (pintype "passive"))
    )
    (net (code "43") (name "Net-(C227-Pad2)") (class "Default")
      (node (ref "C227") (pin "2") (pinfunction "2_2") (pintype "passive"))
      (node (ref "R117") (pin "2") (pinfunction "2_2") (pintype "passive"))
      (node (ref "R119") (pin "2") (pinfunction "2_2") (pintype "passive"))
    )
    (net (code "44") (name "Net-(C228-Pad2)") (class "Default")
      (node (ref "C228") (pin "2") (pinfunction "2_2") (pintype "passive"))
      (node (ref "R118") (pin "2") (pinfunction "2_2") (pintype "passive"))
      (node (ref "R120") (pin "2") (pinfunction "2_2") (pintype "passive"))
    )
    (net (code "45") (name "Net-(C232-Pad2)") (class "Default")
      (node (ref "C232") (pin "2") (pinfunction "2_2") (pintype "passive"))
      (node (ref "R121") (pin "2") (pinfunction "2_2") (pintype "passive"))
      (node (ref "R123") (pin "2") (pinfunction "2_2") (pintype "passive"))
    )
    (net (code "46") (name "Net-(C233-Pad2)") (class "Default")
      (node (ref "C233") (pin "2") (pinfunction "2_2") (pintype "passive"))
      (node (ref "R122") (pin "2") (pinfunction "2_2") (pintype "passive"))
      (node (ref "R124") (pin "2") (pinfunction "2_2") (pintype "passive"))
    )
    (net (code "47") (name "Net-(C237-Pad2)") (class "Default")
      (node (ref "C237") (pin "2") (pinfunction "2_2") (pintype "passive"))
      (node (ref "R125") (pin "2") (pinfunction "2_2") (pintype "passive"))
      (node (ref "R127") (pin "2") (pinfunction "2_2") (pintype "passive"))
    )
    (net (code "48") (name "Net-(C238-Pad2)") (class "Default")
      (node (ref "C238") (pin "2") (pinfunction "2_2") (pintype "passive"))
      (node (ref "R126") (pin "2") (pinfunction "2_2") (pintype "passive"))
      (node (ref "R128") (pin "2") (pinfunction "2_2") (pintype "passive"))
    )
    (net (code "49") (name "Net-(C239-Pad2)") (class "Default")
      (node (ref "C239") (pin "2") (pinfunction "2_2") (pintype "passive"))
      (node (ref "R129") (pin "2") (pinfunction "2_2") (pintype "passive"))
      (node (ref "R131") (pin "2") (pinfunction "2_2") (pintype "passive"))
    )
    (net (code "50") (name "Net-(C240-Pad2)") (class "Default")
      (node (ref "C240") (pin "2") (pinfunction "2_2") (pintype "passive"))
      (node (ref "R130") (pin "2") (pinfunction "2_2") (pintype "passive"))
      (node (ref "R132") (pin "2") (pinfunction "2_2") (pintype "passive"))
    )
    (net (code "51") (name "Net-(C241-Pad2)") (class "Default")
      (node (ref "C241") (pin "2") (pinfunction "2_2") (pintype "passive"))
      (node (ref "R133") (pin "2") (pinfunction "2_2") (pintype "passive"))
      (node (ref "R135") (pin "2") (pinfunction "2_2") (pintype "passive"))
    )
    (net (code "52") (name "Net-(C242-Pad2)") (class "Default")
      (node (ref "C242") (pin "2") (pinfunction "2_2") (pintype "passive"))
      (node (ref "R134") (pin "2") (pinfunction "2_2") (pintype "passive"))
      (node (ref "R136") (pin "2") (pinfunction "2_2") (pintype "passive"))
    )
    (net (code "53") (name "Net-(J4-Pad1)") (class "Default")
      (node (ref "J4") (pin "1") (pinfunction "1_1") (pintype "passive"))
      (node (ref "R101") (pin "2") (pinfunction "2_2") (pintype "passive"))
    )
    (net (code "54") (name "Net-(J5-Pad1)") (class "Default")
      (node (ref "J5") (pin "1") (pinfunction "1_1") (pintype "passive"))
      (node (ref "R112") (pin "2") (pinfunction "2_2") (pintype "passive"))
    )
    (net (code "55") (name "Net-(U19B-FSADJ)") (class "Default")
      (node (ref "R107") (pin "2") (pinfunction "2_2") (pintype "passive"))
      (node (ref "U19") (pin "43") (pinfunction "FSADJ_43") (pintype "passive"))
    )
    (net (code "56") (name "Net-(U19B-REFIO)") (class "Default")
      (node (ref "C224") (pin "2") (pinfunction "2_2") (pintype "passive"))
      (node (ref "U19") (pin "42") (pinfunction "REFIO_42") (pintype "passive"))
    )
    (net (code "57") (name "Net-(U19B-SDIO)") (class "Default")
      (node (ref "R102") (pin "1") (pinfunction "1_1") (pintype "passive"))
      (node (ref "U19") (pin "31") (pinfunction "SDIO_31") (pintype "passive"))
    )
    (net (code "58") (name "Net-(U20A-+IN1)") (class "Default")
      (node (ref "R105") (pin "1") (pinfunction "1_1") (pintype "passive"))
      (node (ref "R106") (pin "2") (pinfunction "2_2") (pintype "passive"))
      (node (ref "U20") (pin "3") (pinfunction "+IN1_3") (pintype "passive"))
    )
    (net (code "59") (name "Net-(U20A--IN1)") (class "Default")
      (node (ref "R100") (pin "1") (pinfunction "1_1") (pintype "passive"))
      (node (ref "R99") (pin "2") (pinfunction "2_2") (pintype "passive"))
      (node (ref "U20") (pin "2") (pinfunction "-IN1_2") (pintype "passive"))
    )
    (net (code "60") (name "Net-(U20A-OUT1)") (class "Default")
      (node (ref "R101") (pin "1") (pinfunction "1_1") (pintype "passive"))
      (node (ref "R99") (pin "1") (pinfunction "1_1") (pintype "passive"))
      (node (ref "U20") (pin "1") (pinfunction "OUT1_1") (pintype "passive"))
    )
    (net (code "61") (name "Net-(U20B-+IN2)") (class "Default")
      (node (ref "R115") (pin "1") (pinfunction "1_1") (pintype "passive"))
      (node (ref "R116") (pin "2") (pinfunction "2_2") (pintype "passive"))
      (node (ref "U20") (pin "5") (pinfunction "+IN2_5") (pintype "passive"))
    )
    (net (code "62") (name "Net-(U20B--IN2)") (class "Default")
      (node (ref "R108") (pin "2") (pinfunction "2_2") (pintype "passive"))
      (node (ref "R109") (pin "1") (pinfunction "1_1") (pintype "passive"))
      (node (ref "U20") (pin "6") (pinfunction "-IN2_6") (pintype "passive"))
    )
    (net (code "63") (name "Net-(U20B-OUT2)") (class "Default")
      (node (ref "R108") (pin "1") (pinfunction "1_1") (pintype "passive"))
      (node (ref "R112") (pin "1") (pinfunction "1_1") (pintype "passive"))
      (node (ref "U20") (pin "7") (pinfunction "OUT2_7") (pintype "passive"))
    )
  )
)
